# motorCTRL.net
KiCad netlist of a schematic drawn in EAGLE
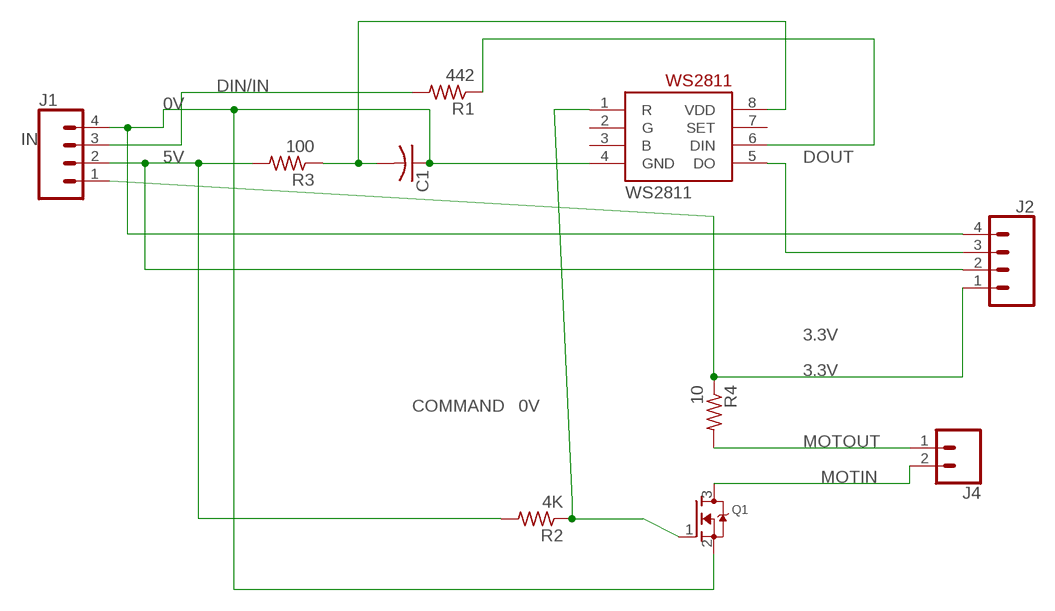
[diagram p0: schematic, sheet 1]

(export (version "E")
  (design (tool "Eeschema 10.0.6"))
  (components
    (comp (ref "C1")
      (value "C-USC0805")
      (footprint "eagle-import:C0805")
      (libsource (lib "eagle-import") (part "C-USC0805"))
    )
    (comp (ref "J1")
      (value "CONN_04")
      (footprint "eagle-import:1X04")
      (libsource (lib "eagle-import") (part "CONN_04"))
    )
    (comp (ref "J2")
      (value "CONN_04")
      (footprint "eagle-import:1X04")
      (libsource (lib "eagle-import") (part "CONN_04"))
    )
    (comp (ref "J4")
      (value "CONN_02")
      (footprint "eagle-import:1X02")
      (libsource (lib "eagle-import") (part "CONN_02"))
    )
    (comp (ref "Q1")
      (value "MOSFET-NREFLOW")
      (footprint "eagle-import:SOT23")
      (libsource (lib "eagle-import") (part "MOSFET-NREFLOW"))
    )
    (comp (ref "R1")
      (value "442")
      (footprint "eagle-import:R0805")
      (libsource (lib "eagle-import") (part "R-US_R0805"))
    )
    (comp (ref "R2")
      (value "4K")
      (footprint "eagle-import:R0805")
      (libsource (lib "eagle-import") (part "R-US_R0805"))
    )
    (comp (ref "R3")
      (value "100")
      (footprint "eagle-import:R0805")
      (libsource (lib "eagle-import") (part "R-US_R0805"))
    )
    (comp (ref "R4")
      (value "10")
      (footprint "eagle-import:R0805")
      (libsource (lib "eagle-import") (part "R-US_R0805"))
    )
    (comp (ref "WS2811")
      (value "WS2811-SOP8")
      (footprint "eagle-import:SO08-SKINNYPADS")
      (libsource (lib "eagle-import") (part "WS2811-SOP8"))
    )
  )
  (nets
    (net (code "1") (name "/0V") (class "Default")
      (node (ref "C1") (pin "1") (pinfunction "1_1") (pintype "passive"))
      (node (ref "J1") (pin "4") (pinfunction "4_4") (pintype "passive"))
      (node (ref "J2") (pin "4") (pinfunction "4_4") (pintype "passive"))
      (node (ref "Q1") (pin "2") (pinfunction "S_2") (pintype "bidirectional"))
      (node (ref "WS2811") (pin "4") (pinfunction "GND_4") (pintype "power_in"))
    )
    (net (code "2") (name "/3.3V") (class "Default")
      (node (ref "J1") (pin "1") (pinfunction "1_1") (pintype "passive"))
      (node (ref "J2") (pin "1") (pinfunction "1_1") (pintype "passive"))
      (node (ref "R4") (pin "1") (pinfunction "1_1") (pintype "passive"))
    )
    (net (code "3") (name "/5V") (class "Default")
      (node (ref "J1") (pin "2") (pinfunction "2_2") (pintype "passive"))
      (node (ref "J2") (pin "2") (pinfunction "2_2") (pintype "passive"))
      (node (ref "R2") (pin "2") (pinfunction "2_2") (pintype "passive"))
      (node (ref "R3") (pin "2") (pinfunction "2_2") (pintype "passive"))
    )
    (net (code "4") (name "/COMMAND") (class "Default")
      (node (ref "Q1") (pin "1") (pinfunction "G_1") (pintype "bidirectional"))
      (node (ref "R2") (pin "1") (pinfunction "1_1") (pintype "passive"))
      (node (ref "WS2811") (pin "1") (pinfunction "R_1") (pintype "open_collector"))
    )
    (net (code "5") (name "/DIN{slash}IN") (class "Default")
      (node (ref "J1") (pin "3") (pinfunction "3_3") (pintype "passive"))
      (node (ref "R1") (pin "2") (pinfunction "2_2") (pintype "passive"))
    )
    (net (code "6") (name "/DOUT") (class "Default")
      (node (ref "J2") (pin "3") (pinfunction "3_3") (pintype "passive"))
      (node (ref "WS2811") (pin "5") (pinfunction "DO_5") (pintype "output"))
    )
    (net (code "7") (name "/MOTIN") (class "Default")
      (node (ref "J4") (pin "2") (pinfunction "2_2") (pintype "passive"))
      (node (ref "Q1") (pin "3") (pinfunction "D_3") (pintype "bidirectional"))
    )
    (net (code "8") (name "/MOTOUT") (class "Default")
      (node (ref "J4") (pin "1") (pinfunction "1_1") (pintype "passive"))
      (node (ref "R4") (pin "2") (pinfunction "2_2") (pintype "passive"))
    )
    (net (code "9") (name "Net-(WS2811-DIN)") (class "Default")
      (node (ref "R1") (pin "1") (pinfunction "1_1") (pintype "passive"))
      (node (ref "WS2811") (pin "6") (pinfunction "DIN_6") (pintype "input"))
    )
    (net (code "10") (name "Net-(WS2811-VDD)") (class "Default")
      (node (ref "C1") (pin "2") (pinfunction "2_2") (pintype "passive"))
      (node (ref "R3") (pin "1") (pinfunction "1_1") (pintype "passive"))
      (node (ref "WS2811") (pin "8") (pinfunction "VDD_8") (pintype "power_in"))
    )
    (net (code "11") (name "unconnected-(WS2811-B-Pad3)") (class "Default")
      (node (ref "WS2811") (pin "3") (pinfunction "B_3") (pintype "open_collector"))
    )
    (net (code "12") (name "unconnected-(WS2811-G-Pad2)") (class "Default")
      (node (ref "WS2811") (pin "2") (pinfunction "G_2") (pintype "open_collector"))
    )
    (net (code "13") (name "unconnected-(WS2811-SET-Pad7)") (class "Default")
      (node (ref "WS2811") (pin "7") (pinfunction "SET_7") (pintype "input"))
    )
  )
)
